# H11L1.net
KiCad netlist of a schematic drawn in EAGLE
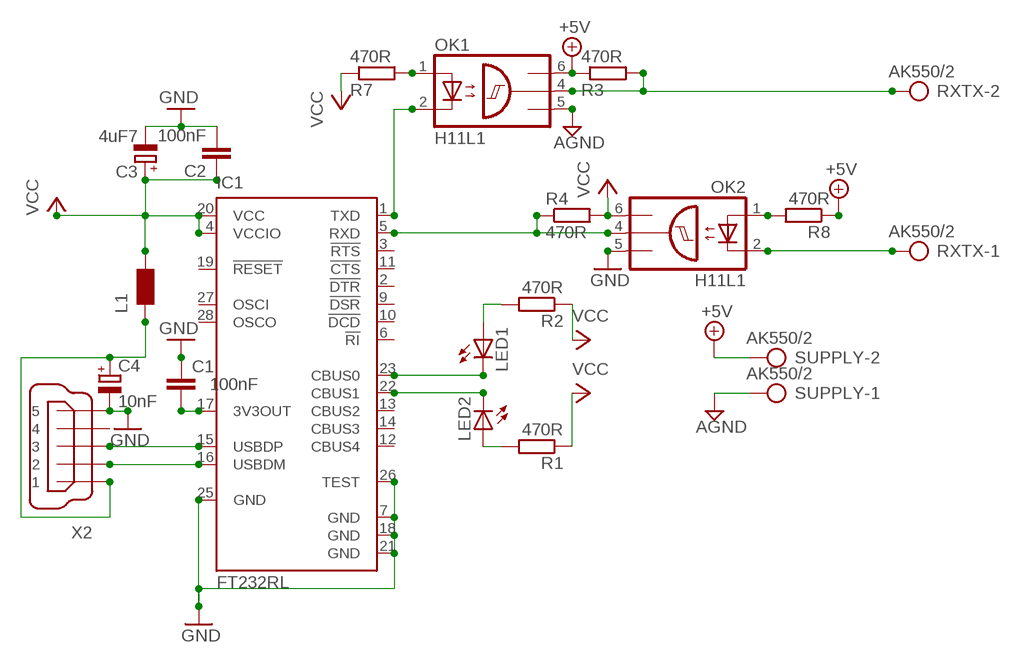
[diagram p0: schematic, sheet 1]

(export (version "E")
  (design (tool "Eeschema 10.0.6"))
  (components
    (comp (ref "C1")
      (value "100nF")
      (footprint "eagle-import:C1206K")
      (libsource (lib "eagle-import") (part "C-EUC1206K"))
    )
    (comp (ref "C2")
      (value "100nF")
      (footprint "eagle-import:C1206K")
      (libsource (lib "eagle-import") (part "C-EUC1206K"))
    )
    (comp (ref "C3")
      (value "4uF7")
      (footprint "eagle-import:140CLH-0810")
      (libsource (lib "eagle-import") (part "CPOL-EU140CLH-0810"))
    )
    (comp (ref "C4")
      (value "10nF")
      (footprint "eagle-import:153CLV-0405")
      (libsource (lib "eagle-import") (part "CPOL-EU153CLV-0405"))
    )
    (comp (ref "IC1")
      (value "FT232RL")
      (footprint "eagle-import:SSOP28")
      (libsource (lib "eagle-import") (part "FT232RL"))
    )
    (comp (ref "L1")
      (value "WE-CBF_1206")
      (footprint "eagle-import:1206")
      (libsource (lib "eagle-import") (part "WE-CBF_1206"))
    )
    (comp (ref "LED1")
      (value "LEDCHIPLED_1206")
      (footprint "eagle-import:CHIPLED_1206")
      (libsource (lib "eagle-import") (part "LEDCHIPLED_1206"))
    )
    (comp (ref "LED2")
      (value "LEDCHIPLED_1206")
      (footprint "eagle-import:CHIPLED_1206")
      (libsource (lib "eagle-import") (part "LEDCHIPLED_1206"))
    )
    (comp (ref "OK1")
      (value "H11L1")
      (footprint "eagle-import:DIL06")
      (libsource (lib "eagle-import") (part "OPI8013"))
    )
    (comp (ref "OK2")
      (value "H11L1")
      (footprint "eagle-import:DIL06")
      (libsource (lib "eagle-import") (part "OPI8013"))
    )
    (comp (ref "R1")
      (value "470R")
      (footprint "eagle-import:M1206")
      (libsource (lib "eagle-import") (part "R-EU_M1206"))
    )
    (comp (ref "R2")
      (value "470R")
      (footprint "eagle-import:M1206")
      (libsource (lib "eagle-import") (part "R-EU_M1206"))
    )
    (comp (ref "R3")
      (value "470R")
      (footprint "eagle-import:M1206")
      (libsource (lib "eagle-import") (part "R-EU_M1206"))
    )
    (comp (ref "R4")
      (value "470R")
      (footprint "eagle-import:M1206")
      (libsource (lib "eagle-import") (part "R-EU_M1206"))
    )
    (comp (ref "R7")
      (value "470R")
      (footprint "eagle-import:M1206")
      (libsource (lib "eagle-import") (part "R-EU_M1206"))
    )
    (comp (ref "R8")
      (value "470R")
      (footprint "eagle-import:M1206")
      (libsource (lib "eagle-import") (part "R-EU_M1206"))
    )
    (comp (ref "RXTX")
      (value "AK550/2")
      (footprint "eagle-import:AK550_2")
      (libsource (lib "eagle-import") (part "AK550/2"))
    )
    (comp (ref "SUPPLY")
      (value "AK550/2")
      (footprint "eagle-import:AK550_2")
      (libsource (lib "eagle-import") (part "AK550/2"))
    )
    (comp (ref "X2")
      (value "MINI-USB-SHIELD-UX60A-MB-5ST")
      (footprint "eagle-import:UX60A-MB-5ST")
      (libsource (lib "eagle-import") (part "MINI-USB-SHIELD-UX60A-MB-5ST"))
    )
  )
  (nets
    (net (code "1") (name "+5V") (class "Default")
      (node (ref "OK1") (pin "6") (pinfunction "VCC_6") (pintype "passive"))
      (node (ref "R3") (pin "1") (pinfunction "1_1") (pintype "passive"))
      (node (ref "R8") (pin "1") (pinfunction "1_1") (pintype "passive"))
      (node (ref "SUPPLY") (pin "2") (pinfunction "KL_2") (pintype "passive"))
    )
    (net (code "2") (name "AGND") (class "Default")
      (node (ref "OK1") (pin "5") (pinfunction "GND_5") (pintype "passive"))
      (node (ref "SUPPLY") (pin "1") (pinfunction "KL_1") (pintype "passive"))
    )
    (net (code "3") (name "GND") (class "Default")
      (node (ref "C1") (pin "1") (pinfunction "1_1") (pintype "passive"))
      (node (ref "C2") (pin "2") (pinfunction "2_2") (pintype "passive"))
      (node (ref "C3") (pin "-") (pinfunction "-_-") (pintype "passive"))
      (node (ref "C4") (pin "-") (pinfunction "-_-") (pintype "passive"))
      (node (ref "IC1") (pin "18") (pinfunction "GND_18") (pintype "input"))
      (node (ref "IC1") (pin "21") (pinfunction "GND_21") (pintype "input"))
      (node (ref "IC1") (pin "25") (pinfunction "GND_25") (pintype "input"))
      (node (ref "IC1") (pin "26") (pinfunction "TEST_26") (pintype "input"))
      (node (ref "IC1") (pin "7") (pinfunction "GND_7") (pintype "input"))
      (node (ref "OK2") (pin "5") (pinfunction "GND_5") (pintype "passive"))
      (node (ref "X2") (pin "5") (pinfunction "5_5") (pintype "input"))
    )
    (net (code "4") (name "Net-(C4-Pad+)") (class "Default")
      (node (ref "C4") (pin "+") (pinfunction "+_+") (pintype "passive"))
      (node (ref "L1") (pin "1") (pinfunction "1_1") (pintype "passive"))
      (node (ref "X2") (pin "1") (pinfunction "1_1") (pintype "input"))
    )
    (net (code "5") (name "Net-(IC1-3V3OUT)") (class "Default")
      (node (ref "C1") (pin "2") (pinfunction "2_2") (pintype "passive"))
      (node (ref "IC1") (pin "17") (pinfunction "3V3OUT_17") (pintype "input"))
    )
    (net (code "6") (name "Net-(IC1-CBUS0)") (class "Default")
      (node (ref "IC1") (pin "23") (pinfunction "CBUS0_23") (pintype "input"))
      (node (ref "LED1") (pin "C") (pinfunction "C_C") (pintype "passive"))
    )
    (net (code "7") (name "Net-(IC1-CBUS1)") (class "Default")
      (node (ref "IC1") (pin "22") (pinfunction "CBUS1_22") (pintype "input"))
      (node (ref "LED2") (pin "C") (pinfunction "C_C") (pintype "passive"))
    )
    (net (code "8") (name "Net-(IC1-RXD)") (class "Default")
      (node (ref "IC1") (pin "5") (pinfunction "RXD_5") (pintype "input"))
      (node (ref "OK2") (pin "4") (pinfunction "OUT_4") (pintype "passive"))
      (node (ref "R4") (pin "1") (pinfunction "1_1") (pintype "passive"))
    )
    (net (code "9") (name "Net-(IC1-TXD)") (class "Default")
      (node (ref "IC1") (pin "1") (pinfunction "TXD_1") (pintype "input"))
      (node (ref "OK1") (pin "2") (pinfunction "C_2") (pintype "passive"))
    )
    (net (code "10") (name "Net-(IC1-USBDM)") (class "Default")
      (node (ref "IC1") (pin "16") (pinfunction "USBDM_16") (pintype "input"))
      (node (ref "X2") (pin "2") (pinfunction "2_2") (pintype "input"))
    )
    (net (code "11") (name "Net-(IC1-USBDP)") (class "Default")
      (node (ref "IC1") (pin "15") (pinfunction "USBDP_15") (pintype "input"))
      (node (ref "X2") (pin "3") (pinfunction "3_3") (pintype "input"))
    )
    (net (code "12") (name "Net-(LED1-PadA)") (class "Default")
      (node (ref "LED1") (pin "A") (pinfunction "A_A") (pintype "passive"))
      (node (ref "R2") (pin "2") (pinfunction "2_2") (pintype "passive"))
    )
    (net (code "13") (name "Net-(LED2-PadA)") (class "Default")
      (node (ref "LED2") (pin "A") (pinfunction "A_A") (pintype "passive"))
      (node (ref "R1") (pin "2") (pinfunction "2_2") (pintype "passive"))
    )
    (net (code "14") (name "Net-(OK1-A)") (class "Default")
      (node (ref "OK1") (pin "1") (pinfunction "A_1") (pintype "passive"))
      (node (ref "R7") (pin "2") (pinfunction "2_2") (pintype "passive"))
    )
    (net (code "15") (name "Net-(OK1-OUT)") (class "Default")
      (node (ref "OK1") (pin "4") (pinfunction "OUT_4") (pintype "passive"))
      (node (ref "R3") (pin "2") (pinfunction "2_2") (pintype "passive"))
      (node (ref "RXTX") (pin "2") (pinfunction "KL_2") (pintype "passive"))
    )
    (net (code "16") (name "Net-(OK2-A)") (class "Default")
      (node (ref "OK2") (pin "1") (pinfunction "A_1") (pintype "passive"))
      (node (ref "R8") (pin "2") (pinfunction "2_2") (pintype "passive"))
    )
    (net (code "17") (name "Net-(OK2-C)") (class "Default")
      (node (ref "OK2") (pin "2") (pinfunction "C_2") (pintype "passive"))
      (node (ref "RXTX") (pin "1") (pinfunction "KL_1") (pintype "passive"))
    )
    (net (code "18") (name "VCC") (class "Default")
      (node (ref "C2") (pin "1") (pinfunction "1_1") (pintype "passive"))
      (node (ref "C3") (pin "+") (pinfunction "+_+") (pintype "passive"))
      (node (ref "IC1") (pin "20") (pinfunction "VCC_20") (pintype "input"))
      (node (ref "IC1") (pin "4") (pinfunction "VCCIO_4") (pintype "input"))
      (node (ref "L1") (pin "2") (pinfunction "2_2") (pintype "passive"))
      (node (ref "OK2") (pin "6") (pinfunction "VCC_6") (pintype "passive"))
      (node (ref "R1") (pin "1") (pinfunction "1_1") (pintype "passive"))
      (node (ref "R2") (pin "1") (pinfunction "1_1") (pintype "passive"))
      (node (ref "R4") (pin "2") (pinfunction "2_2") (pintype "passive"))
      (node (ref "R7") (pin "1") (pinfunction "1_1") (pintype "passive"))
    )
    (net (code "19") (name "unconnected-(IC1-CBUS2-Pad13)") (class "Default")
      (node (ref "IC1") (pin "13") (pinfunction "CBUS2_13") (pintype "input"))
    )
    (net (code "20") (name "unconnected-(IC1-CBUS3-Pad14)") (class "Default")
      (node (ref "IC1") (pin "14") (pinfunction "CBUS3_14") (pintype "input"))
    )
    (net (code "21") (name "unconnected-(IC1-CBUS4-Pad12)") (class "Default")
      (node (ref "IC1") (pin "12") (pinfunction "CBUS4_12") (pintype "input"))
    )
    (net (code "22") (name "unconnected-(IC1-OSCI-Pad27)") (class "Default")
      (node (ref "IC1") (pin "27") (pinfunction "OSCI_27") (pintype "input"))
    )
    (net (code "23") (name "unconnected-(IC1-OSCO-Pad28)") (class "Default")
      (node (ref "IC1") (pin "28") (pinfunction "OSCO_28") (pintype "input"))
    )
    (net (code "24") (name "unconnected-(IC1-~{CTS}-Pad11)") (class "Default")
      (node (ref "IC1") (pin "11") (pinfunction "~{CTS}_11") (pintype "input"))
    )
    (net (code "25") (name "unconnected-(IC1-~{DCD}-Pad10)") (class "Default")
      (node (ref "IC1") (pin "10") (pinfunction "~{DCD}_10") (pintype "input"))
    )
    (net (code "26") (name "unconnected-(IC1-~{DSR}-Pad9)") (class "Default")
      (node (ref "IC1") (pin "9") (pinfunction "~{DSR}_9") (pintype "input"))
    )
    (net (code "27") (name "unconnected-(IC1-~{DTR}-Pad2)") (class "Default")
      (node (ref "IC1") (pin "2") (pinfunction "~{DTR}_2") (pintype "input"))
    )
    (net (code "28") (name "unconnected-(IC1-~{RESET}-Pad19)") (class "Default")
      (node (ref "IC1") (pin "19") (pinfunction "~{RESET}_19") (pintype "input"))
    )
    (net (code "29") (name "unconnected-(IC1-~{RI}-Pad6)") (class "Default")
      (node (ref "IC1") (pin "6") (pinfunction "~{RI}_6") (pintype "input"))
    )
    (net (code "30") (name "unconnected-(IC1-~{RTS}-Pad3)") (class "Default")
      (node (ref "IC1") (pin "3") (pinfunction "~{RTS}_3") (pintype "input"))
    )
    (net (code "31") (name "unconnected-(X2-Pad4)") (class "Default")
      (node (ref "X2") (pin "4") (pinfunction "4_4") (pintype "input"))
    )
  )
)
